# Spinner.net
KiCad netlist of a schematic drawn in EAGLE
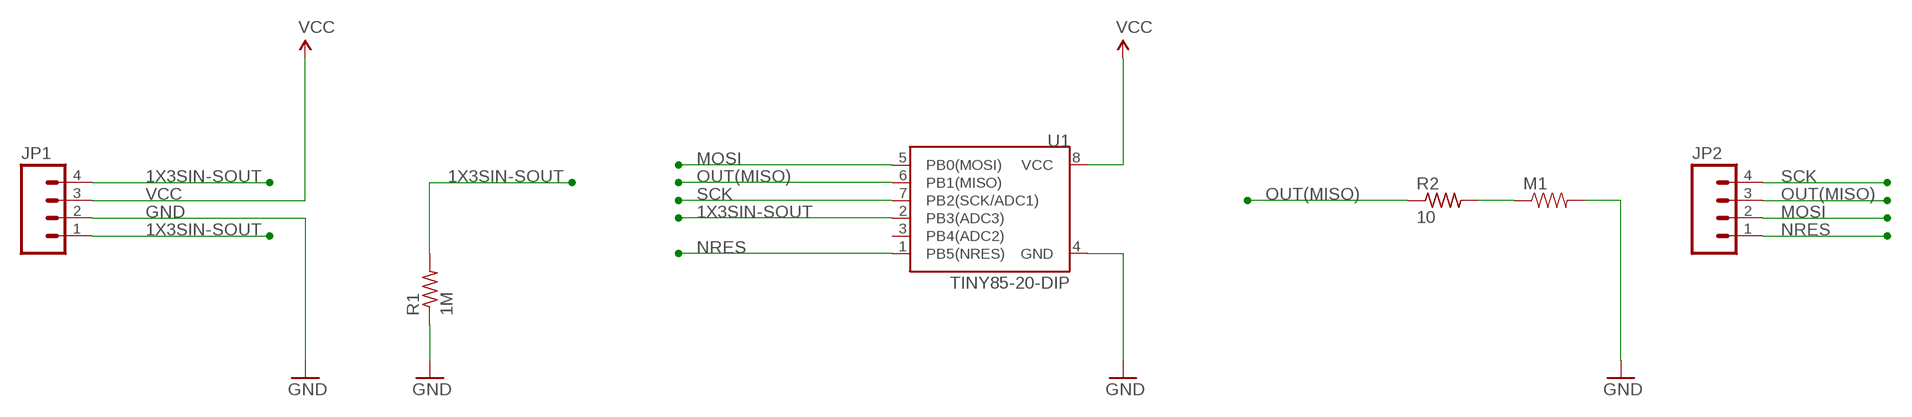
[diagram p0: schematic, sheet 1]

(export (version "E")
  (design (tool "Eeschema 10.0.6"))
  (components
    (comp (ref "JP1")
      (value "M04PTH")
      (footprint "eagle-import:1X04")
      (libsource (lib "eagle-import") (part "M04PTH"))
    )
    (comp (ref "JP2")
      (value "M04PTH")
      (footprint "eagle-import:1X04")
      (libsource (lib "eagle-import") (part "M04PTH"))
    )
    (comp (ref "M1")
      (value "10OHM-1/4W-5%(PTH)VERT-KIT")
      (footprint "eagle-import:AXIAL-0.1EZ")
      (libsource (lib "eagle-import") (part "10OHM-1/4W-5%(PTH)VERT-KIT"))
    )
    (comp (ref "R1")
      (value "1M")
      (footprint "eagle-import:R0603")
      (libsource (lib "eagle-import") (part "R-US_R0603"))
    )
    (comp (ref "R2")
      (value "10")
      (footprint "eagle-import:R0603")
      (libsource (lib "eagle-import") (part "R-US_R0603"))
    )
    (comp (ref "U1")
      (value "TINY85-20-DIP")
      (footprint "eagle-import:DIP08")
      (libsource (lib "eagle-import") (part "ATTINY45TINY85-20-DIP"))
    )
  )
  (nets
    (net (code "1") (name "/1X3SIN-SOUT") (class "Default")
      (node (ref "JP1") (pin "1") (pinfunction "1_1") (pintype "passive"))
      (node (ref "JP1") (pin "4") (pinfunction "4_4") (pintype "passive"))
      (node (ref "R1") (pin "2") (pinfunction "2_2") (pintype "passive"))
      (node (ref "U1") (pin "2") (pinfunction "PB3(ADC3)_2") (pintype "bidirectional"))
    )
    (net (code "2") (name "/MOSI") (class "Default")
      (node (ref "JP2") (pin "2") (pinfunction "2_2") (pintype "passive"))
      (node (ref "U1") (pin "5") (pinfunction "PB0(MOSI)_5") (pintype "bidirectional"))
    )
    (net (code "3") (name "/NRES") (class "Default")
      (node (ref "JP2") (pin "1") (pinfunction "1_1") (pintype "passive"))
      (node (ref "U1") (pin "1") (pinfunction "PB5(NRES)_1") (pintype "bidirectional"))
    )
    (net (code "4") (name "/OUT(MISO)") (class "Default")
      (node (ref "JP2") (pin "3") (pinfunction "3_3") (pintype "passive"))
      (node (ref "R2") (pin "1") (pinfunction "1_1") (pintype "passive"))
      (node (ref "U1") (pin "6") (pinfunction "PB1(MISO)_6") (pintype "bidirectional"))
    )
    (net (code "5") (name "/SCK") (class "Default")
      (node (ref "JP2") (pin "4") (pinfunction "4_4") (pintype "passive"))
      (node (ref "U1") (pin "7") (pinfunction "PB2(SCK/ADC1)_7") (pintype "bidirectional"))
    )
    (net (code "6") (name "GND") (class "Default")
      (node (ref "JP1") (pin "2") (pinfunction "2_2") (pintype "passive"))
      (node (ref "M1") (pin "P$2") (pinfunction "2_P$2") (pintype "passive"))
      (node (ref "R1") (pin "1") (pinfunction "1_1") (pintype "passive"))
      (node (ref "U1") (pin "4") (pinfunction "GND_4") (pintype "bidirectional"))
    )
    (net (code "7") (name "Net-(M1-1)") (class "Default")
      (node (ref "M1") (pin "P$1") (pinfunction "1_P$1") (pintype "passive"))
      (node (ref "R2") (pin "2") (pinfunction "2_2") (pintype "passive"))
    )
    (net (code "8") (name "VCC") (class "Default")
      (node (ref "JP1") (pin "3") (pinfunction "3_3") (pintype "passive"))
      (node (ref "U1") (pin "8") (pinfunction "VCC_8") (pintype "bidirectional"))
    )
    (net (code "9") (name "unconnected-(U1-PB4(ADC2)-Pad3)") (class "Default")
      (node (ref "U1") (pin "3") (pinfunction "PB4(ADC2)_3") (pintype "bidirectional"))
    )
  )
)
